# Mother.net
KiCad netlist of a schematic drawn in Altium Designer
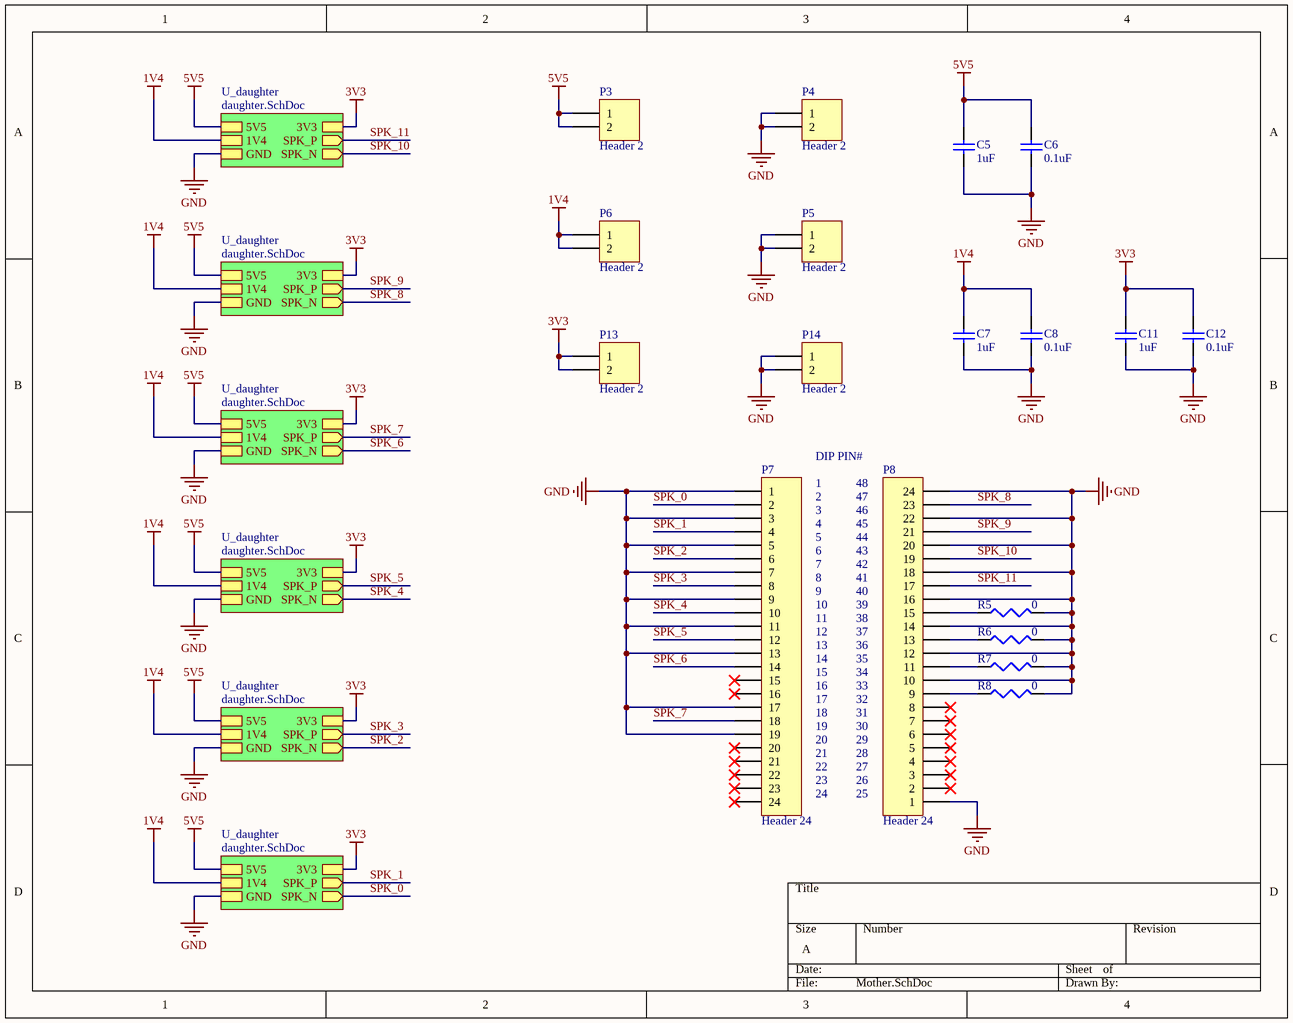
[diagram p0: Mother.SchDoc]

(export (version "E")
  (design (tool "Eeschema 10.0.6"))
  (components
    (comp (ref "C5")
      (value "1uF")
      (footprint "SMD-0805")
      (description "Ceramic Capacitor 0805 Imperial (2012 Metric)")
      (libsource (lib "LCR") (part "CAP0805"))
    )
    (comp (ref "C6")
      (value "0.1uF")
      (footprint "SMD-0603")
      (description "Ceramic Capacitor 0603")
      (libsource (lib "LCR") (part "CAP0603"))
    )
    (comp (ref "C7")
      (value "1uF")
      (footprint "SMD-0805")
      (description "Ceramic Capacitor 0805 Imperial (2012 Metric)")
      (libsource (lib "LCR") (part "CAP0805"))
    )
    (comp (ref "C8")
      (value "0.1uF")
      (footprint "SMD-0603")
      (description "Ceramic Capacitor 0603")
      (libsource (lib "LCR") (part "CAP0603"))
    )
    (comp (ref "C11")
      (value "1uF")
      (footprint "SMD-0805")
      (description "Ceramic Capacitor 0805 Imperial (2012 Metric)")
      (libsource (lib "LCR") (part "CAP0805"))
    )
    (comp (ref "C12")
      (value "0.1uF")
      (footprint "SMD-0603")
      (description "Ceramic Capacitor 0603")
      (libsource (lib "LCR") (part "CAP0603"))
    )
    (comp (ref "P3")
      (value "Header 2")
      (footprint "HDR1X2")
      (description "Header, 2-Pin")
      (fields (field (name "PUBLISHER") "Altium Limited"))
      (libsource (lib "Miscellaneous Connectors") (part "Header 2"))
    )
    (comp (ref "P4")
      (value "Header 2")
      (footprint "HDR1X2")
      (description "Header, 2-Pin")
      (fields (field (name "PUBLISHER") "Altium Limited"))
      (libsource (lib "Miscellaneous Connectors") (part "Header 2"))
    )
    (comp (ref "P5")
      (value "Header 2")
      (footprint "HDR1X2")
      (description "Header, 2-Pin")
      (fields (field (name "PUBLISHER") "Altium Limited"))
      (libsource (lib "Miscellaneous Connectors") (part "Header 2"))
    )
    (comp (ref "P6")
      (value "Header 2")
      (footprint "HDR1X2")
      (description "Header, 2-Pin")
      (fields (field (name "PUBLISHER") "Altium Limited"))
      (libsource (lib "Miscellaneous Connectors") (part "Header 2"))
    )
    (comp (ref "P7")
      (value "Header 24")
      (footprint "HDR1X24")
      (description "Header, 24-Pin")
      (fields (field (name "PUBLISHER") "Altium Limited"))
      (libsource (lib "") (part "Header 24_1"))
    )
    (comp (ref "P8")
      (value "Header 24")
      (footprint "HDR1X24")
      (description "Header, 24-Pin")
      (fields (field (name "PUBLISHER") "Altium Limited"))
      (libsource (lib "Miscellaneous Connectors") (part "Header 24"))
    )
    (comp (ref "P13")
      (value "Header 2")
      (footprint "HDR1X2")
      (description "Header, 2-Pin")
      (fields (field (name "PUBLISHER") "Altium Limited"))
      (libsource (lib "Miscellaneous Connectors") (part "Header 2"))
    )
    (comp (ref "P14")
      (value "Header 2")
      (footprint "HDR1X2")
      (description "Header, 2-Pin")
      (fields (field (name "PUBLISHER") "Altium Limited"))
      (libsource (lib "Miscellaneous Connectors") (part "Header 2"))
    )
    (comp (ref "R5")
      (value "0")
      (footprint "SMD-0603")
      (description "Resistor-0603")
      (libsource (lib "LCR") (part "RES0603"))
    )
    (comp (ref "R6")
      (value "0")
      (footprint "SMD-0603")
      (description "Resistor-0603")
      (libsource (lib "LCR") (part "RES0603"))
    )
    (comp (ref "R7")
      (value "0")
      (footprint "SMD-0603")
      (description "Resistor-0603")
      (libsource (lib "LCR") (part "RES0603"))
    )
    (comp (ref "R8")
      (value "0")
      (footprint "SMD-0603")
      (description "Resistor-0603")
      (libsource (lib "LCR") (part "RES0603"))
    )
  )
  (nets
    (net (code "1") (name "/SPK_0") (class "Default")
      (node (ref "P7") (pin "2") (pinfunction "2_2") (pintype "passive"))
    )
    (net (code "2") (name "/SPK_1") (class "Default")
      (node (ref "P7") (pin "4") (pinfunction "4_4") (pintype "passive"))
    )
    (net (code "3") (name "/SPK_2") (class "Default")
      (node (ref "P7") (pin "6") (pinfunction "6_6") (pintype "passive"))
    )
    (net (code "4") (name "/SPK_3") (class "Default")
      (node (ref "P7") (pin "8") (pinfunction "8_8") (pintype "passive"))
    )
    (net (code "5") (name "/SPK_4") (class "Default")
      (node (ref "P7") (pin "10") (pinfunction "10_10") (pintype "passive"))
    )
    (net (code "6") (name "/SPK_5") (class "Default")
      (node (ref "P7") (pin "12") (pinfunction "12_12") (pintype "passive"))
    )
    (net (code "7") (name "/SPK_6") (class "Default")
      (node (ref "P7") (pin "14") (pinfunction "14_14") (pintype "passive"))
    )
    (net (code "8") (name "/SPK_7") (class "Default")
      (node (ref "P7") (pin "18") (pinfunction "18_18") (pintype "passive"))
    )
    (net (code "9") (name "/SPK_8") (class "Default")
      (node (ref "P8") (pin "23") (pinfunction "23_23") (pintype "passive"))
    )
    (net (code "10") (name "/SPK_9") (class "Default")
      (node (ref "P8") (pin "21") (pinfunction "21_21") (pintype "passive"))
    )
    (net (code "11") (name "/SPK_10") (class "Default")
      (node (ref "P8") (pin "19") (pinfunction "19_19") (pintype "passive"))
    )
    (net (code "12") (name "/SPK_11") (class "Default")
      (node (ref "P8") (pin "17") (pinfunction "17_17") (pintype "passive"))
    )
    (net (code "13") (name "1V4") (class "Default")
      (node (ref "C7") (pin "2") (pinfunction "2_2") (pintype "passive"))
      (node (ref "C8") (pin "2") (pinfunction "2_2") (pintype "passive"))
      (node (ref "P6") (pin "1") (pinfunction "1_1") (pintype "passive"))
      (node (ref "P6") (pin "2") (pinfunction "2_2") (pintype "passive"))
    )
    (net (code "14") (name "3V3") (class "Default")
      (node (ref "C11") (pin "2") (pinfunction "2_2") (pintype "passive"))
      (node (ref "C12") (pin "2") (pinfunction "2_2") (pintype "passive"))
      (node (ref "P13") (pin "1") (pinfunction "1_1") (pintype "passive"))
      (node (ref "P13") (pin "2") (pinfunction "2_2") (pintype "passive"))
    )
    (net (code "15") (name "5V5") (class "Default")
      (node (ref "C5") (pin "2") (pinfunction "2_2") (pintype "passive"))
      (node (ref "C6") (pin "2") (pinfunction "2_2") (pintype "passive"))
      (node (ref "P3") (pin "1") (pinfunction "1_1") (pintype "passive"))
      (node (ref "P3") (pin "2") (pinfunction "2_2") (pintype "passive"))
    )
    (net (code "16") (name "GND") (class "Default")
      (node (ref "C11") (pin "1") (pinfunction "1_1") (pintype "passive"))
      (node (ref "C12") (pin "1") (pinfunction "1_1") (pintype "passive"))
      (node (ref "C5") (pin "1") (pinfunction "1_1") (pintype "passive"))
      (node (ref "C6") (pin "1") (pinfunction "1_1") (pintype "passive"))
      (node (ref "C7") (pin "1") (pinfunction "1_1") (pintype "passive"))
      (node (ref "C8") (pin "1") (pinfunction "1_1") (pintype "passive"))
      (node (ref "P14") (pin "1") (pinfunction "1_1") (pintype "passive"))
      (node (ref "P14") (pin "2") (pinfunction "2_2") (pintype "passive"))
      (node (ref "P4") (pin "1") (pinfunction "1_1") (pintype "passive"))
      (node (ref "P4") (pin "2") (pinfunction "2_2") (pintype "passive"))
      (node (ref "P5") (pin "1") (pinfunction "1_1") (pintype "passive"))
      (node (ref "P5") (pin "2") (pinfunction "2_2") (pintype "passive"))
      (node (ref "P7") (pin "1") (pinfunction "1_1") (pintype "passive"))
      (node (ref "P7") (pin "11") (pinfunction "11_11") (pintype "passive"))
      (node (ref "P7") (pin "13") (pinfunction "13_13") (pintype "passive"))
      (node (ref "P7") (pin "17") (pinfunction "17_17") (pintype "passive"))
      (node (ref "P7") (pin "19") (pinfunction "19_19") (pintype "passive"))
      (node (ref "P7") (pin "3") (pinfunction "3_3") (pintype "passive"))
      (node (ref "P7") (pin "5") (pinfunction "5_5") (pintype "passive"))
      (node (ref "P7") (pin "7") (pinfunction "7_7") (pintype "passive"))
      (node (ref "P7") (pin "9") (pinfunction "9_9") (pintype "passive"))
      (node (ref "P8") (pin "1") (pinfunction "1_1") (pintype "passive"))
      (node (ref "P8") (pin "10") (pinfunction "10_10") (pintype "passive"))
      (node (ref "P8") (pin "12") (pinfunction "12_12") (pintype "passive"))
      (node (ref "P8") (pin "14") (pinfunction "14_14") (pintype "passive"))
      (node (ref "P8") (pin "16") (pinfunction "16_16") (pintype "passive"))
      (node (ref "P8") (pin "18") (pinfunction "18_18") (pintype "passive"))
      (node (ref "P8") (pin "20") (pinfunction "20_20") (pintype "passive"))
      (node (ref "P8") (pin "22") (pinfunction "22_22") (pintype "passive"))
      (node (ref "P8") (pin "24") (pinfunction "24_24") (pintype "passive"))
      (node (ref "R5") (pin "2") (pinfunction "2_2") (pintype "passive"))
      (node (ref "R6") (pin "2") (pinfunction "2_2") (pintype "passive"))
      (node (ref "R7") (pin "2") (pinfunction "2_2") (pintype "passive"))
      (node (ref "R8") (pin "2") (pinfunction "2_2") (pintype "passive"))
    )
    (net (code "17") (name "Net-(P8-Pad9)") (class "Default")
      (node (ref "P8") (pin "9") (pinfunction "9_9") (pintype "passive"))
      (node (ref "R8") (pin "1") (pinfunction "1_1") (pintype "passive"))
    )
    (net (code "18") (name "Net-(P8-Pad11)") (class "Default")
      (node (ref "P8") (pin "11") (pinfunction "11_11") (pintype "passive"))
      (node (ref "R7") (pin "1") (pinfunction "1_1") (pintype "passive"))
    )
    (net (code "19") (name "Net-(P8-Pad13)") (class "Default")
      (node (ref "P8") (pin "13") (pinfunction "13_13") (pintype "passive"))
      (node (ref "R6") (pin "1") (pinfunction "1_1") (pintype "passive"))
    )
    (net (code "20") (name "Net-(P8-Pad15)") (class "Default")
      (node (ref "P8") (pin "15") (pinfunction "15_15") (pintype "passive"))
      (node (ref "R5") (pin "1") (pinfunction "1_1") (pintype "passive"))
    )
    (net (code "21") (name "unconnected-(P7-Pad15)") (class "Default")
      (node (ref "P7") (pin "15") (pinfunction "15_15") (pintype "passive+no_connect"))
    )
    (net (code "22") (name "unconnected-(P7-Pad16)") (class "Default")
      (node (ref "P7") (pin "16") (pinfunction "16_16") (pintype "passive+no_connect"))
    )
    (net (code "23") (name "unconnected-(P7-Pad20)") (class "Default")
      (node (ref "P7") (pin "20") (pinfunction "20_20") (pintype "passive+no_connect"))
    )
    (net (code "24") (name "unconnected-(P7-Pad21)") (class "Default")
      (node (ref "P7") (pin "21") (pinfunction "21_21") (pintype "passive+no_connect"))
    )
    (net (code "25") (name "unconnected-(P7-Pad22)") (class "Default")
      (node (ref "P7") (pin "22") (pinfunction "22_22") (pintype "passive+no_connect"))
    )
    (net (code "26") (name "unconnected-(P7-Pad23)") (class "Default")
      (node (ref "P7") (pin "23") (pinfunction "23_23") (pintype "passive+no_connect"))
    )
    (net (code "27") (name "unconnected-(P7-Pad24)") (class "Default")
      (node (ref "P7") (pin "24") (pinfunction "24_24") (pintype "passive+no_connect"))
    )
    (net (code "28") (name "unconnected-(P8-Pad2)") (class "Default")
      (node (ref "P8") (pin "2") (pinfunction "2_2") (pintype "passive+no_connect"))
    )
    (net (code "29") (name "unconnected-(P8-Pad3)") (class "Default")
      (node (ref "P8") (pin "3") (pinfunction "3_3") (pintype "passive+no_connect"))
    )
    (net (code "30") (name "unconnected-(P8-Pad4)") (class "Default")
      (node (ref "P8") (pin "4") (pinfunction "4_4") (pintype "passive+no_connect"))
    )
    (net (code "31") (name "unconnected-(P8-Pad5)") (class "Default")
      (node (ref "P8") (pin "5") (pinfunction "5_5") (pintype "passive+no_connect"))
    )
    (net (code "32") (name "unconnected-(P8-Pad6)") (class "Default")
      (node (ref "P8") (pin "6") (pinfunction "6_6") (pintype "passive+no_connect"))
    )
    (net (code "33") (name "unconnected-(P8-Pad7)") (class "Default")
      (node (ref "P8") (pin "7") (pinfunction "7_7") (pintype "passive+no_connect"))
    )
    (net (code "34") (name "unconnected-(P8-Pad8)") (class "Default")
      (node (ref "P8") (pin "8") (pinfunction "8_8") (pintype "passive+no_connect"))
    )
  )
)
